# RS485_PART.net
KiCad netlist of a schematic drawn in Altium Designer
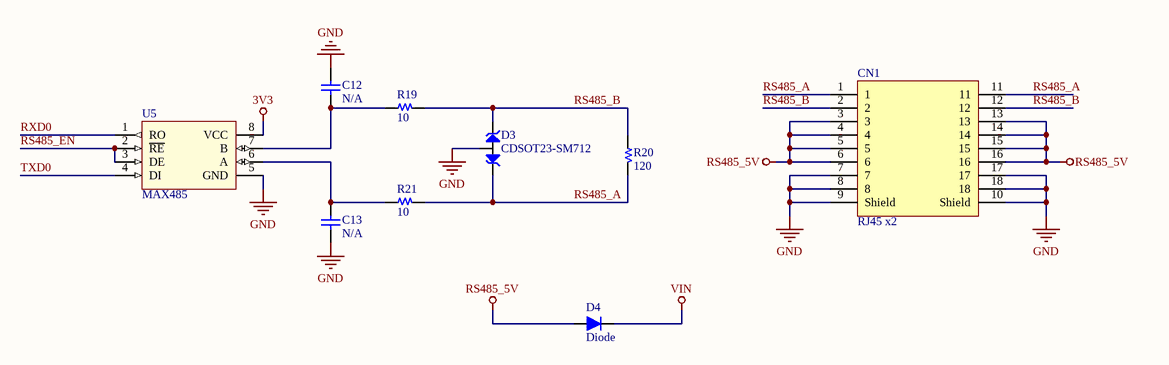
[diagram p0: RS485_PART.SchDoc]

(export (version "E")
  (design (tool "Eeschema 10.0.6"))
  (components
    (comp (ref "C12")
      (value "N/A")
      (footprint "C 1206")
      (description "Capacitor non-pol")
      (libsource (lib "chipfc_libs") (part "Capacitor NP"))
    )
    (comp (ref "C13")
      (value "N/A")
      (footprint "C 1206")
      (description "Capacitor non-pol")
      (libsource (lib "chipfc_libs") (part "Capacitor NP"))
    )
    (comp (ref "CN1")
      (value "RJ45 x2")
      (footprint "CONN/RJ45/x2")
      (description "Connector RJ45 X2")
      (libsource (lib "connectors") (part "CON RJ45 x2"))
    )
    (comp (ref "D3")
      (value "CDSOT23-SM712")
      (footprint "SOT-23")
      (description "TVS DIODE 7V/12V 14V/26V SOT23-3")
      (libsource (lib "chipfc_libs") (part "CDSOT23-SM712"))
    )
    (comp (ref "D4")
      (value "Diode")
      (footprint "SOD123")
      (description "Default Diode")
      (libsource (lib "chipfc_libs") (part "Diode"))
    )
    (comp (ref "R19")
      (value "10")
      (footprint "R 0603")
      (description "Resistor")
      (libsource (lib "chipfc_libs") (part "Resistor"))
    )
    (comp (ref "R20")
      (value "120")
      (footprint "R 0603")
      (description "Resistor")
      (libsource (lib "chipfc_libs") (part "Resistor"))
    )
    (comp (ref "R21")
      (value "10")
      (footprint "R 0603")
      (description "Resistor")
      (libsource (lib "chipfc_libs") (part "Resistor"))
    )
    (comp (ref "U5")
      (value "MAX485")
      (footprint "SOIC-8")
      (description "Low-Power, Slew-Rate-Limited  RS-485/RS-422 Transceivers")
      (libsource (lib "bs_libs") (part "MAX485"))
    )
  )
  (nets
    (net (code "1") (name "/RS485_A") (class "Default")
      (node (ref "CN1") (pin "1") (pinfunction "1_1") (pintype "passive"))
      (node (ref "CN1") (pin "11") (pinfunction "11_11") (pintype "passive"))
      (node (ref "D3") (pin "1") (pinfunction "IO1_1") (pintype "passive"))
      (node (ref "R20") (pin "2") (pinfunction "2_2") (pintype "passive"))
      (node (ref "R21") (pin "2") (pinfunction "2_2") (pintype "passive"))
    )
    (net (code "2") (name "/RS485_B") (class "Default")
      (node (ref "CN1") (pin "12") (pinfunction "12_12") (pintype "passive"))
      (node (ref "CN1") (pin "2") (pinfunction "2_2") (pintype "passive"))
      (node (ref "D3") (pin "2") (pinfunction "IO2_2") (pintype "passive"))
      (node (ref "R19") (pin "2") (pinfunction "2_2") (pintype "passive"))
      (node (ref "R20") (pin "1") (pinfunction "1_1") (pintype "passive"))
    )
    (net (code "3") (name "/RS485_EN") (class "Default")
      (node (ref "U5") (pin "2") (pinfunction "~{RE}_2") (pintype "input"))
      (node (ref "U5") (pin "3") (pinfunction "DE_3") (pintype "input"))
    )
    (net (code "4") (name "/RXD0") (class "Default")
      (node (ref "U5") (pin "1") (pinfunction "RO_1") (pintype "output"))
    )
    (net (code "5") (name "/TXD0") (class "Default")
      (node (ref "U5") (pin "4") (pinfunction "DI_4") (pintype "input"))
    )
    (net (code "6") (name "3V3") (class "Default")
      (node (ref "U5") (pin "8") (pinfunction "VCC_8") (pintype "passive"))
    )
    (net (code "7") (name "GND") (class "Default")
      (node (ref "C12") (pin "1") (pinfunction "1_1") (pintype "passive"))
      (node (ref "C13") (pin "2") (pinfunction "2_2") (pintype "passive"))
      (node (ref "CN1") (pin "10") (pinfunction "Shield_10") (pintype "passive"))
      (node (ref "CN1") (pin "17") (pinfunction "17_17") (pintype "passive"))
      (node (ref "CN1") (pin "18") (pinfunction "18_18") (pintype "passive"))
      (node (ref "CN1") (pin "7") (pinfunction "7_7") (pintype "passive"))
      (node (ref "CN1") (pin "8") (pinfunction "8_8") (pintype "passive"))
      (node (ref "CN1") (pin "9") (pinfunction "Shield_9") (pintype "passive"))
      (node (ref "D3") (pin "3") (pinfunction "COM_3") (pintype "passive"))
      (node (ref "U5") (pin "5") (pinfunction "GND_5") (pintype "passive"))
    )
    (net (code "8") (name "Net-(U5-A)") (class "Default")
      (node (ref "C13") (pin "1") (pinfunction "1_1") (pintype "passive"))
      (node (ref "R21") (pin "1") (pinfunction "1_1") (pintype "passive"))
      (node (ref "U5") (pin "6") (pinfunction "A_6") (pintype "bidirectional"))
    )
    (net (code "9") (name "Net-(U5-B)") (class "Default")
      (node (ref "C12") (pin "2") (pinfunction "2_2") (pintype "passive"))
      (node (ref "R19") (pin "1") (pinfunction "1_1") (pintype "passive"))
      (node (ref "U5") (pin "7") (pinfunction "B_7") (pintype "bidirectional"))
    )
    (net (code "10") (name "RS485_5V") (class "Default")
      (node (ref "CN1") (pin "13") (pinfunction "13_13") (pintype "passive"))
      (node (ref "CN1") (pin "14") (pinfunction "14_14") (pintype "passive"))
      (node (ref "CN1") (pin "15") (pinfunction "15_15") (pintype "passive"))
      (node (ref "CN1") (pin "16") (pinfunction "16_16") (pintype "passive"))
      (node (ref "CN1") (pin "3") (pinfunction "3_3") (pintype "passive"))
      (node (ref "CN1") (pin "4") (pinfunction "4_4") (pintype "passive"))
      (node (ref "CN1") (pin "5") (pinfunction "5_5") (pintype "passive"))
      (node (ref "CN1") (pin "6") (pinfunction "6_6") (pintype "passive"))
      (node (ref "D4") (pin "1") (pinfunction "A_1") (pintype "passive"))
    )
    (net (code "11") (name "VIN") (class "Default")
      (node (ref "D4") (pin "2") (pinfunction "K_2") (pintype "passive"))
    )
  )
)
